# PCB_Cajero_10.net
KiCad netlist of a schematic drawn in EAGLE
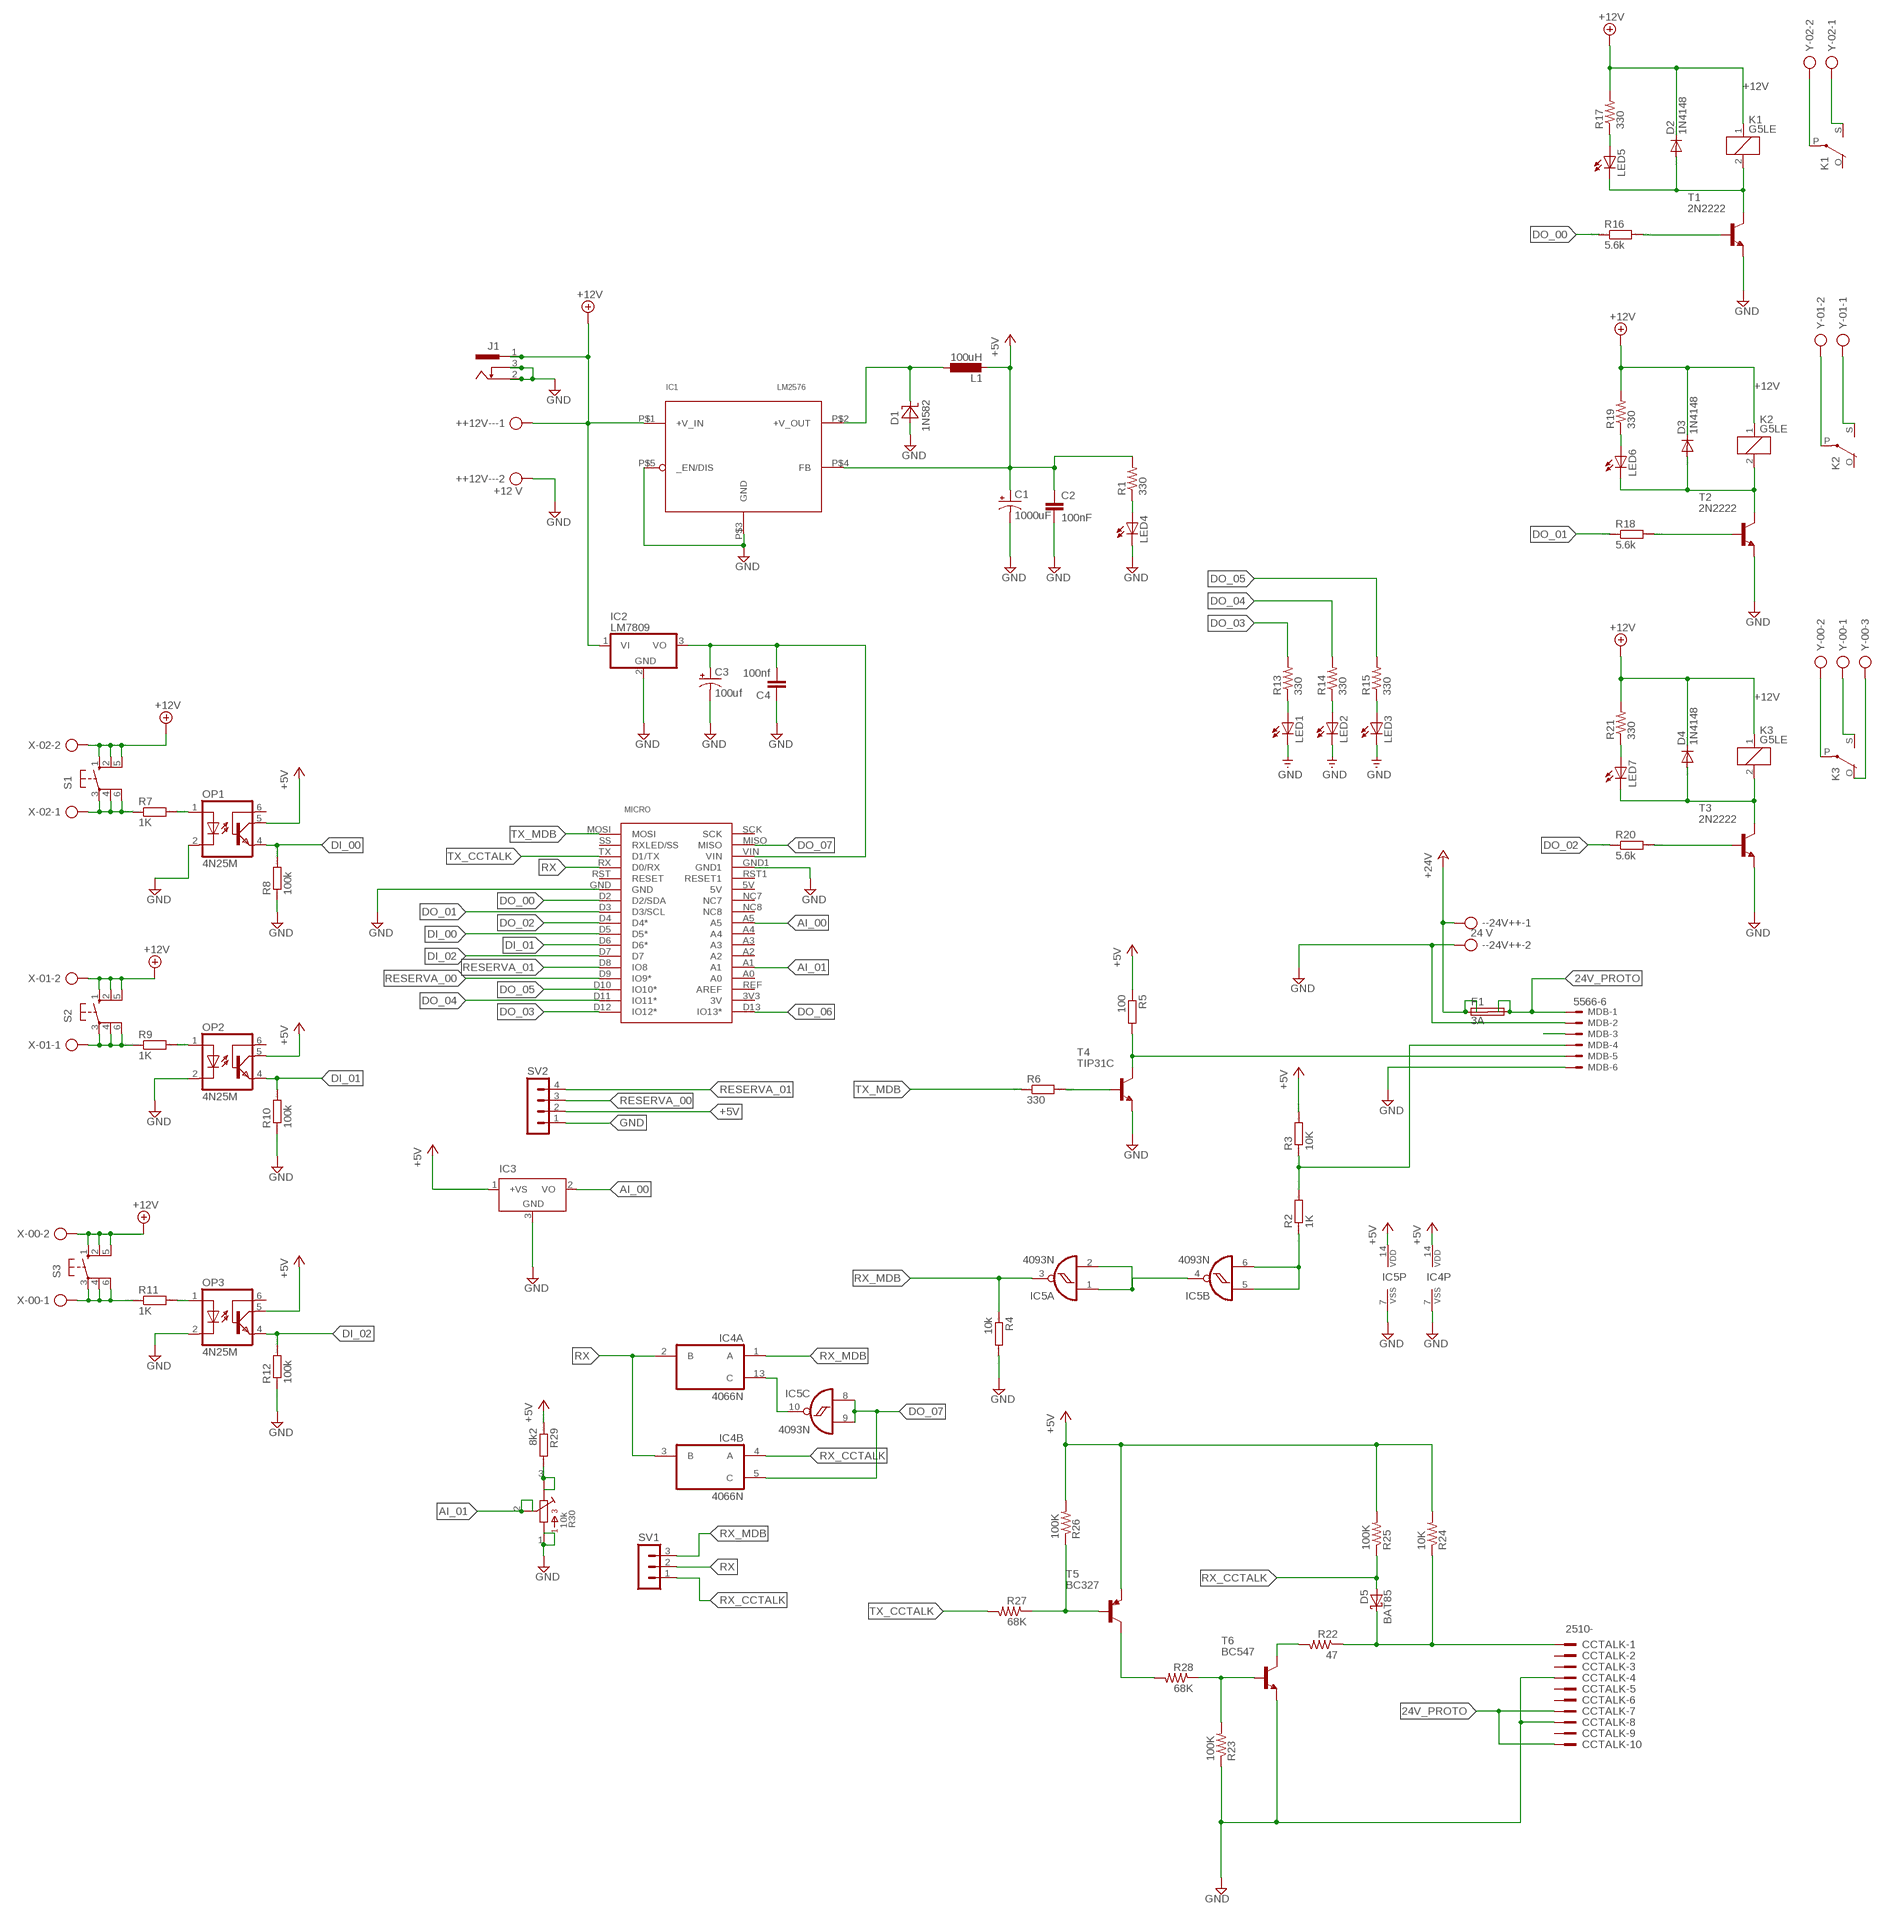
[diagram p0: schematic, sheet 1]

(export (version "E")
  (design (tool "Eeschema 10.0.6"))
  (components
    (comp (ref "++12V--")
      (value "+12 V")
      (footprint "eagle-import:AK500_2")
      (libsource (lib "eagle-import") (part "AK500/2"))
    )
    (comp (ref "--24V++")
      (value "24 V")
      (footprint "eagle-import:AK500_2")
      (libsource (lib "eagle-import") (part "AK500/2"))
    )
    (comp (ref "C1")
      (value "1000uF")
      (footprint "eagle-import:E5-5")
      (libsource (lib "eagle-import") (part "rcl_334_CPOL-USE5-5"))
    )
    (comp (ref "C2")
      (value "100nF")
      (footprint "eagle-import:C2.5-3")
      (libsource (lib "eagle-import") (part "C2,5-3"))
    )
    (comp (ref "C3")
      (value "100uf")
      (footprint "eagle-import:E2,5-6")
      (libsource (lib "eagle-import") (part "CPOL-USE2.5-6"))
    )
    (comp (ref "C4")
      (value "100nf")
      (footprint "eagle-import:C2.5-3")
      (libsource (lib "eagle-import") (part "C2,5-3"))
    )
    (comp (ref "CCTALK")
      (value "2510-")
      (footprint "eagle-import:PAK100_2500-10")
      (fields (field (name "MF") "3M") (field (name "MPN") "2510-6002UB"))
      (libsource (lib "eagle-import") (part "2510-"))
    )
    (comp (ref "D1")
      (value "1N582")
      (footprint "eagle-import:1N582_")
      (libsource (lib "eagle-import") (part "1N582"))
    )
    (comp (ref "D2")
      (value "1N4148")
      (footprint "eagle-import:DO35-7")
      (libsource (lib "eagle-import") (part "1N4148DO35-7"))
    )
    (comp (ref "D3")
      (value "1N4148")
      (footprint "eagle-import:DO35-7")
      (libsource (lib "eagle-import") (part "1N4148DO35-7"))
    )
    (comp (ref "D4")
      (value "1N4148")
      (footprint "eagle-import:DO35-7")
      (libsource (lib "eagle-import") (part "1N4148DO35-7"))
    )
    (comp (ref "D5")
      (value "BAT85")
      (footprint "eagle-import:SOD68")
      (libsource (lib "eagle-import") (part "BAT85"))
    )
    (comp (ref "F1")
      (value "3A")
      (footprint "eagle-import:SHK20L")
      (libsource (lib "eagle-import") (part "SHK20L"))
    )
    (comp (ref "IC1")
      (value "LM2576")
      (footprint "eagle-import:TO220_SEP")
      (libsource (lib "eagle-import") (part "LM2576-T05E"))
    )
    (comp (ref "IC2")
      (value "LM7809")
      (footprint "eagle-import:TO-220V")
      (libsource (lib "eagle-import") (part "LM7809"))
    )
    (comp (ref "IC3")
      (value "LM35CZ")
      (footprint "eagle-import:TO92")
      (libsource (lib "eagle-import") (part "LM35CZ"))
    )
    (comp (ref "IC4")
      (value "4066N")
      (footprint "eagle-import:DIL14")
      (libsource (lib "eagle-import") (part "4066N"))
    )
    (comp (ref "IC5")
      (value "4093N")
      (footprint "eagle-import:DIL14")
      (fields (field (name "SPICEPREFIX") "J"))
      (libsource (lib "eagle-import") (part "4093N"))
    )
    (comp (ref "J1")
      (value "KLDVX-0202-A")
      (footprint "eagle-import:KLDVX-0202-A")
      (libsource (lib "eagle-import") (part "KLDVX-0202-A"))
    )
    (comp (ref "K1")
      (value "G5LE")
      (footprint "eagle-import:G5LE")
      (libsource (lib "eagle-import") (part "G5LE"))
    )
    (comp (ref "K2")
      (value "G5LE")
      (footprint "eagle-import:G5LE")
      (libsource (lib "eagle-import") (part "G5LE"))
    )
    (comp (ref "K3")
      (value "G5LE")
      (footprint "eagle-import:G5LE")
      (libsource (lib "eagle-import") (part "G5LE"))
    )
    (comp (ref "L1")
      (value "100uH")
      (footprint "eagle-import:DO3316P")
      (libsource (lib "eagle-import") (part "DO3316P"))
    )
    (comp (ref "LED1")
      (value "LED5MM")
      (footprint "eagle-import:LED5MM")
      (libsource (lib "eagle-import") (part "LED5MM"))
    )
    (comp (ref "LED2")
      (value "LED5MM")
      (footprint "eagle-import:LED5MM")
      (libsource (lib "eagle-import") (part "LED5MM"))
    )
    (comp (ref "LED3")
      (value "LED5MM")
      (footprint "eagle-import:LED5MM")
      (libsource (lib "eagle-import") (part "LED5MM"))
    )
    (comp (ref "LED4")
      (value "LED5MM")
      (footprint "eagle-import:LED5MM")
      (libsource (lib "eagle-import") (part "LED5MM"))
    )
    (comp (ref "LED5")
      (value "LED5MM")
      (footprint "eagle-import:LED5MM")
      (libsource (lib "eagle-import") (part "LED5MM"))
    )
    (comp (ref "LED6")
      (value "LED5MM")
      (footprint "eagle-import:LED5MM")
      (libsource (lib "eagle-import") (part "LED5MM"))
    )
    (comp (ref "LED7")
      (value "LED5MM")
      (footprint "eagle-import:LED5MM")
      (libsource (lib "eagle-import") (part "LED5MM"))
    )
    (comp (ref "MDB")
      (value "5566-6")
      (footprint "eagle-import:5566-6")
      (fields (field (name "MF") "MOLEX") (field (name "MPN") "95566-61002"))
      (libsource (lib "eagle-import") (part "5566-6"))
    )
    (comp (ref "MICRO")
      (value "ARDUINO_MICROFOOTPRINT")
      (footprint "eagle-import:ARDUINO-MICRO")
      (libsource (lib "eagle-import") (part "ARDUINO_MICROFOOTPRINT"))
    )
    (comp (ref "OP1")
      (value "4N25M")
      (footprint "eagle-import:DIL06")
      (fields (field (name "MPN") "4N25-M"))
      (libsource (lib "eagle-import") (part "4N?M25"))
    )
    (comp (ref "OP2")
      (value "4N25M")
      (footprint "eagle-import:DIL06")
      (fields (field (name "MPN") "4N25-M"))
      (libsource (lib "eagle-import") (part "4N?M25"))
    )
    (comp (ref "OP3")
      (value "4N25M")
      (footprint "eagle-import:DIL06")
      (fields (field (name "MPN") "4N25-M"))
      (libsource (lib "eagle-import") (part "4N?M25"))
    )
    (comp (ref "R1")
      (value "330")
      (footprint "eagle-import:0207_7")
      (libsource (lib "eagle-import") (part "R-US_0207/7"))
    )
    (comp (ref "R2")
      (value "1K")
      (footprint "eagle-import:0204_7")
      (libsource (lib "eagle-import") (part "R0204/7"))
    )
    (comp (ref "R3")
      (value "10K")
      (footprint "eagle-import:0204_7")
      (libsource (lib "eagle-import") (part "R0204/7"))
    )
    (comp (ref "R4")
      (value "10k")
      (footprint "eagle-import:0204_7")
      (libsource (lib "eagle-import") (part "R0204/7"))
    )
    (comp (ref "R5")
      (value "100")
      (footprint "eagle-import:0309_10")
      (libsource (lib "eagle-import") (part "R-EU_0309/10"))
    )
    (comp (ref "R6")
      (value "330")
      (footprint "eagle-import:0204_7")
      (libsource (lib "eagle-import") (part "R0204/7"))
    )
    (comp (ref "R7")
      (value "1K")
      (footprint "eagle-import:0204_7")
      (libsource (lib "eagle-import") (part "R0204/7"))
    )
    (comp (ref "R8")
      (value "100k")
      (footprint "eagle-import:0204_7")
      (libsource (lib "eagle-import") (part "R0204/7"))
    )
    (comp (ref "R9")
      (value "1K")
      (footprint "eagle-import:0204_7")
      (libsource (lib "eagle-import") (part "R0204/7"))
    )
    (comp (ref "R10")
      (value "100k")
      (footprint "eagle-import:0204_7")
      (libsource (lib "eagle-import") (part "R0204/7"))
    )
    (comp (ref "R11")
      (value "1K")
      (footprint "eagle-import:0204_7")
      (libsource (lib "eagle-import") (part "R0204/7"))
    )
    (comp (ref "R12")
      (value "100k")
      (footprint "eagle-import:0204_7")
      (libsource (lib "eagle-import") (part "R0204/7"))
    )
    (comp (ref "R13")
      (value "330")
      (footprint "eagle-import:0207_7")
      (libsource (lib "eagle-import") (part "R-US_0207/7"))
    )
    (comp (ref "R14")
      (value "330")
      (footprint "eagle-import:0207_7")
      (libsource (lib "eagle-import") (part "R-US_0207/7"))
    )
    (comp (ref "R15")
      (value "330")
      (footprint "eagle-import:0207_7")
      (libsource (lib "eagle-import") (part "R-US_0207/7"))
    )
    (comp (ref "R16")
      (value "5.6k")
      (footprint "eagle-import:0204_7")
      (libsource (lib "eagle-import") (part "R0204/7"))
    )
    (comp (ref "R17")
      (value "330")
      (footprint "eagle-import:0207_7")
      (libsource (lib "eagle-import") (part "R-US_0207/7"))
    )
    (comp (ref "R18")
      (value "5.6k")
      (footprint "eagle-import:0204_7")
      (libsource (lib "eagle-import") (part "R0204/7"))
    )
    (comp (ref "R19")
      (value "330")
      (footprint "eagle-import:0207_7")
      (libsource (lib "eagle-import") (part "R-US_0207/7"))
    )
    (comp (ref "R20")
      (value "5.6k")
      (footprint "eagle-import:0204_7")
      (libsource (lib "eagle-import") (part "R0204/7"))
    )
    (comp (ref "R21")
      (value "330")
      (footprint "eagle-import:0207_7")
      (libsource (lib "eagle-import") (part "R-US_0207/7"))
    )
    (comp (ref "R22")
      (value "47")
      (footprint "eagle-import:0204_7")
      (libsource (lib "eagle-import") (part "R-US_0204/7"))
    )
    (comp (ref "R23")
      (value "100K")
      (footprint "eagle-import:0204_7")
      (libsource (lib "eagle-import") (part "R-US_0204/7"))
    )
    (comp (ref "R24")
      (value "10K")
      (footprint "eagle-import:0204_7")
      (libsource (lib "eagle-import") (part "R-US_0204/7"))
    )
    (comp (ref "R25")
      (value "100K")
      (footprint "eagle-import:0204_7")
      (libsource (lib "eagle-import") (part "R-US_0204/7"))
    )
    (comp (ref "R26")
      (value "100K")
      (footprint "eagle-import:0204_7")
      (libsource (lib "eagle-import") (part "R-US_0204/7"))
    )
    (comp (ref "R27")
      (value "68K")
      (footprint "eagle-import:0204_7")
      (libsource (lib "eagle-import") (part "R-US_0204/7"))
    )
    (comp (ref "R28")
      (value "68K")
      (footprint "eagle-import:0204_7")
      (libsource (lib "eagle-import") (part "R-US_0204/7"))
    )
    (comp (ref "R29")
      (value "8k2")
      (footprint "eagle-import:0204_7")
      (libsource (lib "eagle-import") (part "R0204/7"))
    )
    (comp (ref "R30")
      (value "10k")
      (footprint "eagle-import:3386-MULTI")
      (libsource (lib "eagle-import") (part "3386"))
    )
    (comp (ref "S1")
      (value "10-XX")
      (footprint "eagle-import:B3F-10XX")
      (fields (field (name "MPN") "B3F-1000"))
      (libsource (lib "eagle-import") (part "10-XX"))
    )
    (comp (ref "S2")
      (value "10-XX")
      (footprint "eagle-import:B3F-10XX")
      (fields (field (name "MPN") "B3F-1000"))
      (libsource (lib "eagle-import") (part "10-XX"))
    )
    (comp (ref "S3")
      (value "10-XX")
      (footprint "eagle-import:B3F-10XX")
      (fields (field (name "MPN") "B3F-1000"))
      (libsource (lib "eagle-import") (part "10-XX"))
    )
    (comp (ref "SV1")
      (value "MA03-1")
      (footprint "eagle-import:MA03-1")
      (libsource (lib "eagle-import") (part "MA03-1"))
    )
    (comp (ref "SV2")
      (value "MA04-1")
      (footprint "eagle-import:MA04-1")
      (libsource (lib "eagle-import") (part "MA04-1"))
    )
    (comp (ref "T1")
      (value "2N2222")
      (footprint "eagle-import:TO18")
      (libsource (lib "eagle-import") (part "2N2222"))
    )
    (comp (ref "T2")
      (value "2N2222")
      (footprint "eagle-import:TO18")
      (libsource (lib "eagle-import") (part "2N2222"))
    )
    (comp (ref "T3")
      (value "2N2222")
      (footprint "eagle-import:TO18")
      (libsource (lib "eagle-import") (part "2N2222"))
    )
    (comp (ref "T4")
      (value "TIP31C")
      (footprint "eagle-import:TO-220V")
      (libsource (lib "eagle-import") (part "TIP31C"))
    )
    (comp (ref "T5")
      (value "BC327")
      (footprint "eagle-import:TO92")
      (libsource (lib "eagle-import") (part "BC327"))
    )
    (comp (ref "T6")
      (value "BC547")
      (footprint "eagle-import:TO92")
      (libsource (lib "eagle-import") (part "BC547"))
    )
    (comp (ref "X-00")
      (value "AK500/2")
      (footprint "eagle-import:AK500_2")
      (libsource (lib "eagle-import") (part "AK500/2"))
    )
    (comp (ref "X-01")
      (value "AK500/2")
      (footprint "eagle-import:AK500_2")
      (libsource (lib "eagle-import") (part "AK500/2"))
    )
    (comp (ref "X-02")
      (value "AK500/2")
      (footprint "eagle-import:AK500_2")
      (libsource (lib "eagle-import") (part "AK500/2"))
    )
    (comp (ref "Y-00")
      (value "AK500/3")
      (footprint "eagle-import:AK500_3")
      (libsource (lib "eagle-import") (part "AK500/3"))
    )
    (comp (ref "Y-01")
      (value "AK500/2")
      (footprint "eagle-import:AK500_2")
      (libsource (lib "eagle-import") (part "AK500/2"))
    )
    (comp (ref "Y-02")
      (value "AK500/2")
      (footprint "eagle-import:AK500_2")
      (libsource (lib "eagle-import") (part "AK500/2"))
    )
  )
  (nets
    (net (code "1") (name "+5V") (class "Default")
      (node (ref "C1") (pin "+") (pinfunction "+_+") (pintype "passive"))
      (node (ref "C2") (pin "1") (pinfunction "1_1") (pintype "passive"))
      (node (ref "IC1") (pin "P$4") (pinfunction "FB_P$4") (pintype "input"))
      (node (ref "IC3") (pin "1") (pinfunction "+VS_1") (pintype "input"))
      (node (ref "IC4") (pin "14") (pinfunction "VDD_14") (pintype "power_in"))
      (node (ref "IC5") (pin "14") (pinfunction "VDD_14") (pintype "power_in"))
      (node (ref "L1") (pin "1") (pinfunction "1_1") (pintype "passive"))
      (node (ref "OP1") (pin "5") (pinfunction "COL_5") (pintype "passive"))
      (node (ref "OP2") (pin "5") (pinfunction "COL_5") (pintype "passive"))
      (node (ref "OP3") (pin "5") (pinfunction "COL_5") (pintype "passive"))
      (node (ref "R1") (pin "2") (pinfunction "2_2") (pintype "passive"))
      (node (ref "R24") (pin "2") (pinfunction "2_2") (pintype "passive"))
      (node (ref "R25") (pin "2") (pinfunction "2_2") (pintype "passive"))
      (node (ref "R26") (pin "2") (pinfunction "2_2") (pintype "passive"))
      (node (ref "R29") (pin "1") (pinfunction "1_1") (pintype "passive"))
      (node (ref "R3") (pin "2") (pinfunction "2_2") (pintype "passive"))
      (node (ref "R5") (pin "1") (pinfunction "1_1") (pintype "passive"))
      (node (ref "SV2") (pin "2") (pinfunction "2_2") (pintype "passive"))
      (node (ref "T5") (pin "1") (pinfunction "E_1") (pintype "passive"))
    )
    (net (code "2") (name "+12V") (class "Default")
      (node (ref "++12V--") (pin "1") (pinfunction "KL_1") (pintype "passive"))
      (node (ref "D2") (pin "C") (pinfunction "C_C") (pintype "passive"))
      (node (ref "D3") (pin "C") (pinfunction "C_C") (pintype "passive"))
      (node (ref "D4") (pin "C") (pinfunction "C_C") (pintype "passive"))
      (node (ref "IC1") (pin "P$1") (pinfunction "+V_IN_P$1") (pintype "input"))
      (node (ref "IC2") (pin "1") (pinfunction "VI_1") (pintype "input"))
      (node (ref "J1") (pin "1") (pinfunction "1_1") (pintype "passive"))
      (node (ref "J1") (pin "1@1") (pinfunction "1_1@1") (pintype "passive"))
      (node (ref "K1") (pin "1") (pinfunction "1_1") (pintype "passive"))
      (node (ref "K2") (pin "1") (pinfunction "1_1") (pintype "passive"))
      (node (ref "K3") (pin "1") (pinfunction "1_1") (pintype "passive"))
      (node (ref "R17") (pin "2") (pinfunction "2_2") (pintype "passive"))
      (node (ref "R19") (pin "2") (pinfunction "2_2") (pintype "passive"))
      (node (ref "R21") (pin "2") (pinfunction "2_2") (pintype "passive"))
      (node (ref "S1") (pin "1") (pinfunction "S_1") (pintype "passive"))
      (node (ref "S1") (pin "2") (pinfunction "S1_2") (pintype "passive"))
      (node (ref "S1") (pin "5") (pinfunction "S2_5") (pintype "passive"))
      (node (ref "S2") (pin "1") (pinfunction "S_1") (pintype "passive"))
      (node (ref "S2") (pin "2") (pinfunction "S1_2") (pintype "passive"))
      (node (ref "S2") (pin "5") (pinfunction "S2_5") (pintype "passive"))
      (node (ref "S3") (pin "1") (pinfunction "S_1") (pintype "passive"))
      (node (ref "S3") (pin "2") (pinfunction "S1_2") (pintype "passive"))
      (node (ref "S3") (pin "5") (pinfunction "S2_5") (pintype "passive"))
      (node (ref "X-00") (pin "2") (pinfunction "KL_2") (pintype "passive"))
      (node (ref "X-01") (pin "2") (pinfunction "KL_2") (pintype "passive"))
      (node (ref "X-02") (pin "2") (pinfunction "KL_2") (pintype "passive"))
    )
    (net (code "3") (name "+24V") (class "Default")
      (node (ref "--24V++") (pin "1") (pinfunction "KL_1") (pintype "passive"))
      (node (ref "F1") (pin "1A") (pinfunction "1A_1A") (pintype "passive"))
      (node (ref "F1") (pin "1B") (pinfunction "1B_1B") (pintype "passive"))
    )
    (net (code "4") (name "24V_PROTO") (class "Default")
      (node (ref "CCTALK") (pin "10") (pinfunction "KL_10") (pintype "passive"))
      (node (ref "CCTALK") (pin "7") (pinfunction "KL_7") (pintype "passive"))
      (node (ref "F1") (pin "2A") (pinfunction "2A_2A") (pintype "passive"))
      (node (ref "F1") (pin "2B") (pinfunction "2B_2B") (pintype "passive"))
      (node (ref "MDB") (pin "1") (pinfunction "S_1") (pintype "passive"))
    )
    (net (code "5") (name "AI_00") (class "Default")
      (node (ref "IC3") (pin "2") (pinfunction "VO_2") (pintype "input"))
      (node (ref "MICRO") (pin "A5") (pinfunction "A5_A5") (pintype "bidirectional"))
    )
    (net (code "6") (name "AI_01") (class "Default")
      (node (ref "MICRO") (pin "A1") (pinfunction "A1_A1") (pintype "bidirectional"))
      (node (ref "R30") (pin "2") (pinfunction "2_2") (pintype "passive"))
      (node (ref "R30") (pin "5") (pinfunction "5_5") (pintype "passive"))
    )
    (net (code "7") (name "DI_00") (class "Default")
      (node (ref "MICRO") (pin "D5") (pinfunction "D5*_D5") (pintype "bidirectional"))
      (node (ref "OP1") (pin "4") (pinfunction "EMI_4") (pintype "passive"))
      (node (ref "R8") (pin "2") (pinfunction "2_2") (pintype "passive"))
    )
    (net (code "8") (name "DI_01") (class "Default")
      (node (ref "MICRO") (pin "D6") (pinfunction "D6*_D6") (pintype "bidirectional"))
      (node (ref "OP2") (pin "4") (pinfunction "EMI_4") (pintype "passive"))
      (node (ref "R10") (pin "2") (pinfunction "2_2") (pintype "passive"))
    )
    (net (code "9") (name "DI_02") (class "Default")
      (node (ref "MICRO") (pin "D7") (pinfunction "D7_D7") (pintype "bidirectional"))
      (node (ref "OP3") (pin "4") (pinfunction "EMI_4") (pintype "passive"))
      (node (ref "R12") (pin "2") (pinfunction "2_2") (pintype "passive"))
    )
    (net (code "10") (name "DO_00") (class "Default")
      (node (ref "MICRO") (pin "D2") (pinfunction "D2/SDA_D2") (pintype "bidirectional"))
      (node (ref "R16") (pin "1") (pinfunction "1_1") (pintype "passive"))
    )
    (net (code "11") (name "DO_01") (class "Default")
      (node (ref "MICRO") (pin "D3") (pinfunction "D3/SCL_D3") (pintype "bidirectional"))
      (node (ref "R18") (pin "1") (pinfunction "1_1") (pintype "passive"))
    )
    (net (code "12") (name "DO_02") (class "Default")
      (node (ref "MICRO") (pin "D4") (pinfunction "D4*_D4") (pintype "bidirectional"))
      (node (ref "R20") (pin "1") (pinfunction "1_1") (pintype "passive"))
    )
    (net (code "13") (name "DO_03") (class "Default")
      (node (ref "MICRO") (pin "D12") (pinfunction "IO12*_D12") (pintype "bidirectional"))
      (node (ref "R13") (pin "2") (pinfunction "2_2") (pintype "passive"))
    )
    (net (code "14") (name "DO_04") (class "Default")
      (node (ref "MICRO") (pin "D11") (pinfunction "IO11*_D11") (pintype "bidirectional"))
      (node (ref "R14") (pin "2") (pinfunction "2_2") (pintype "passive"))
    )
    (net (code "15") (name "DO_05") (class "Default")
      (node (ref "MICRO") (pin "D10") (pinfunction "IO10*_D10") (pintype "bidirectional"))
      (node (ref "R15") (pin "2") (pinfunction "2_2") (pintype "passive"))
    )
    (net (code "16") (name "DO_06") (class "Default")
      (node (ref "MICRO") (pin "D13") (pinfunction "IO13*_D13") (pintype "bidirectional"))
    )
    (net (code "17") (name "DO_07") (class "Default")
      (node (ref "IC4") (pin "5") (pinfunction "C_5") (pintype "input"))
      (node (ref "IC5") (pin "8") (pinfunction "I0_8") (pintype "input"))
      (node (ref "IC5") (pin "9") (pinfunction "I1_9") (pintype "input"))
      (node (ref "MICRO") (pin "MISO") (pinfunction "MISO_MISO") (pintype "bidirectional"))
    )
    (net (code "18") (name "GND") (class "Default")
      (node (ref "++12V--") (pin "2") (pinfunction "KL_2") (pintype "passive"))
      (node (ref "--24V++") (pin "2") (pinfunction "KL_2") (pintype "passive"))
      (node (ref "C1") (pin "-") (pinfunction "-_-") (pintype "passive"))
      (node (ref "C2") (pin "2") (pinfunction "2_2") (pintype "passive"))
      (node (ref "C3") (pin "-") (pinfunction "-_-") (pintype "passive"))
      (node (ref "C4") (pin "1") (pinfunction "1_1") (pintype "passive"))
      (node (ref "CCTALK") (pin "4") (pinfunction "KL_4") (pintype "passive"))
      (node (ref "CCTALK") (pin "8") (pinfunction "KL_8") (pintype "passive"))
      (node (ref "D1") (pin "A") (pinfunction "A_A") (pintype "passive"))
      (node (ref "IC1") (pin "P$3") (pinfunction "GND_P$3") (pintype "power_in"))
      (node (ref "IC1") (pin "P$5") (pinfunction "_EN/DIS_P$5") (pintype "input"))
      (node (ref "IC2") (pin "2") (pinfunction "GND_2") (pintype "passive"))
      (node (ref "IC3") (pin "3") (pinfunction "GND_3") (pintype "power_in"))
      (node (ref "IC4") (pin "7") (pinfunction "VSS_7") (pintype "power_in"))
      (node (ref "IC5") (pin "7") (pinfunction "VSS_7") (pintype "power_in"))
      (node (ref "J1") (pin "2") (pinfunction "2_2") (pintype "passive"))
      (node (ref "J1") (pin "2@1") (pinfunction "2_2@1") (pintype "passive"))
      (node (ref "J1") (pin "3") (pinfunction "3_3") (pintype "passive"))
      (node (ref "J1") (pin "3@1") (pinfunction "3_3@1") (pintype "passive"))
      (node (ref "LED1") (pin "K") (pinfunction "C_K") (pintype "passive"))
      (node (ref "LED2") (pin "K") (pinfunction "C_K") (pintype "passive"))
      (node (ref "LED3") (pin "K") (pinfunction "C_K") (pintype "passive"))
      (node (ref "LED4") (pin "K") (pinfunction "C_K") (pintype "passive"))
      (node (ref "MDB") (pin "2") (pinfunction "S_2") (pintype "passive"))
      (node (ref "MDB") (pin "6") (pinfunction "S_6") (pintype "passive"))
      (node (ref "MICRO") (pin "GND") (pinfunction "GND_GND") (pintype "bidirectional"))
      (node (ref "MICRO") (pin "GND1") (pinfunction "GND1_GND1") (pintype "bidirectional"))
      (node (ref "OP1") (pin "2") (pinfunction "C_2") (pintype "passive"))
      (node (ref "OP2") (pin "2") (pinfunction "C_2") (pintype "passive"))
      (node (ref "OP3") (pin "2") (pinfunction "C_2") (pintype "passive"))
      (node (ref "R10") (pin "1") (pinfunction "1_1") (pintype "passive"))
      (node (ref "R12") (pin "1") (pinfunction "1_1") (pintype "passive"))
      (node (ref "R23") (pin "1") (pinfunction "1_1") (pintype "passive"))
      (node (ref "R30") (pin "1") (pinfunction "1_1") (pintype "passive"))
      (node (ref "R30") (pin "4") (pinfunction "4_4") (pintype "passive"))
      (node (ref "R4") (pin "2") (pinfunction "2_2") (pintype "passive"))
      (node (ref "R8") (pin "1") (pinfunction "1_1") (pintype "passive"))
      (node (ref "SV2") (pin "1") (pinfunction "1_1") (pintype "passive"))
      (node (ref "T1") (pin "1") (pinfunction "E_1") (pintype "passive"))
      (node (ref "T2") (pin "1") (pinfunction "E_1") (pintype "passive"))
      (node (ref "T3") (pin "1") (pinfunction "E_1") (pintype "passive"))
      (node (ref "T4") (pin "3") (pinfunction "E_3") (pintype "passive"))
      (node (ref "T6") (pin "1") (pinfunction "E_1") (pintype "passive"))
    )
    (net (code "19") (name "Net-(CCTALKA-KL)") (class "Default")
      (node (ref "CCTALK") (pin "1") (pinfunction "KL_1") (pintype "passive"))
      (node (ref "D5") (pin "C") (pinfunction "K_C") (pintype "passive"))
      (node (ref "R22") (pin "1") (pinfunction "1_1") (pintype "passive"))
      (node (ref "R24") (pin "1") (pinfunction "1_1") (pintype "passive"))
    )
    (net (code "20") (name "Net-(IC1-+V_OUT)") (class "Default")
      (node (ref "D1") (pin "C") (pinfunction "C_C") (pintype "passive"))
      (node (ref "IC1") (pin "P$2") (pinfunction "+V_OUT_P$2") (pintype "output"))
      (node (ref "L1") (pin "2") (pinfunction "2_2") (pintype "passive"))
    )
    (net (code "21") (name "Net-(IC2-VO)") (class "Default")
      (node (ref "C3") (pin "+") (pinfunction "+_+") (pintype "passive"))
      (node (ref "C4") (pin "2") (pinfunction "2_2") (pintype "passive"))
      (node (ref "IC2") (pin "3") (pinfunction "VO_3") (pintype "passive"))
      (node (ref "MICRO") (pin "VIN") (pinfunction "VIN_VIN") (pintype "bidirectional"))
    )
    (net (code "22") (name "Net-(IC4A-C)") (class "Default")
      (node (ref "IC4") (pin "13") (pinfunction "C_13") (pintype "input"))
      (node (ref "IC5") (pin "10") (pinfunction "O_10") (pintype "output"))
    )
    (net (code "23") (name "Net-(IC5A-I0)") (class "Default")
      (node (ref "IC5") (pin "1") (pinfunction "I0_1") (pintype "input"))
      (node (ref "IC5") (pin "2") (pinfunction "I1_2") (pintype "input"))
      (node (ref "IC5") (pin "4") (pinfunction "O_4") (pintype "output"))
    )
    (net (code "24") (name "Net-(IC5B-I0)") (class "Default")
      (node (ref "IC5") (pin "5") (pinfunction "I0_5") (pintype "input"))
      (node (ref "IC5") (pin "6") (pinfunction "I1_6") (pintype "input"))
      (node (ref "R2") (pin "1") (pinfunction "1_1") (pintype "passive"))
    )
    (net (code "25") (name "Net-(LED1-PadA)") (class "Default")
      (node (ref "LED1") (pin "A") (pinfunction "A_A") (pintype "passive"))
      (node (ref "R13") (pin "1") (pinfunction "1_1") (pintype "passive"))
    )
    (net (code "26") (name "Net-(LED2-PadA)") (class "Default")
      (node (ref "LED2") (pin "A") (pinfunction "A_A") (pintype "passive"))
      (node (ref "R14") (pin "1") (pinfunction "1_1") (pintype "passive"))
    )
    (net (code "27") (name "Net-(LED3-PadA)") (class "Default")
      (node (ref "LED3") (pin "A") (pinfunction "A_A") (pintype "passive"))
      (node (ref "R15") (pin "1") (pinfunction "1_1") (pintype "passive"))
    )
    (net (code "28") (name "Net-(LED4-PadA)") (class "Default")
      (node (ref "LED4") (pin "A") (pinfunction "A_A") (pintype "passive"))
      (node (ref "R1") (pin "1") (pinfunction "1_1") (pintype "passive"))
    )
    (net (code "29") (name "Net-(LED5-C)") (class "Default")
      (node (ref "D2") (pin "A") (pinfunction "A_A") (pintype "passive"))
      (node (ref "K1") (pin "2") (pinfunction "2_2") (pintype "passive"))
      (node (ref "LED5") (pin "K") (pinfunction "C_K") (pintype "passive"))
      (node (ref "T1") (pin "3") (pinfunction "C_3") (pintype "passive"))
    )
    (net (code "30") (name "Net-(LED5-PadA)") (class "Default")
      (node (ref "LED5") (pin "A") (pinfunction "A_A") (pintype "passive"))
      (node (ref "R17") (pin "1") (pinfunction "1_1") (pintype "passive"))
    )
    (net (code "31") (name "Net-(LED6-C)") (class "Default")
      (node (ref "D3") (pin "A") (pinfunction "A_A") (pintype "passive"))
      (node (ref "K2") (pin "2") (pinfunction "2_2") (pintype "passive"))
      (node (ref "LED6") (pin "K") (pinfunction "C_K") (pintype "passive"))
      (node (ref "T2") (pin "3") (pinfunction "C_3") (pintype "passive"))
    )
    (net (code "32") (name "Net-(LED6-PadA)") (class "Default")
      (node (ref "LED6") (pin "A") (pinfunction "A_A") (pintype "passive"))
      (node (ref "R19") (pin "1") (pinfunction "1_1") (pintype "passive"))
    )
    (net (code "33") (name "Net-(LED7-C)") (class "Default")
      (node (ref "D4") (pin "A") (pinfunction "A_A") (pintype "passive"))
      (node (ref "K3") (pin "2") (pinfunction "2_2") (pintype "passive"))
      (node (ref "LED7") (pin "K") (pinfunction "C_K") (pintype "passive"))
      (node (ref "T3") (pin "3") (pinfunction "C_3") (pintype "passive"))
    )
    (net (code "34") (name "Net-(LED7-PadA)") (class "Default")
      (node (ref "LED7") (pin "A") (pinfunction "A_A") (pintype "passive"))
      (node (ref "R21") (pin "1") (pinfunction "1_1") (pintype "passive"))
    )
    (net (code "35") (name "Net-(MDBD-S)") (class "Default")
      (node (ref "MDB") (pin "4") (pinfunction "S_4") (pintype "passive"))
      (node (ref "R2") (pin "2") (pinfunction "2_2") (pintype "passive"))
      (node (ref "R3") (pin "1") (pinfunction "1_1") (pintype "passive"))
    )
    (net (code "36") (name "Net-(MDBE-S)") (class "Default")
      (node (ref "MDB") (pin "5") (pinfunction "S_5") (pintype "passive"))
      (node (ref "R5") (pin "2") (pinfunction "2_2") (pintype "passive"))
      (node (ref "T4") (pin "2") (pinfunction "C_2") (pintype "passive"))
    )
    (net (code "37") (name "Net-(OP1-A)") (class "Default")
      (node (ref "OP1") (pin "1") (pinfunction "A_1") (pintype "passive"))
      (node (ref "R7") (pin "2") (pinfunction "2_2") (pintype "passive"))
    )
    (net (code "38") (name "Net-(OP2-A)") (class "Default")
      (node (ref "OP2") (pin "1") (pinfunction "A_1") (pintype "passive"))
      (node (ref "R9") (pin "2") (pinfunction "2_2") (pintype "passive"))
    )
    (net (code "39") (name "Net-(OP3-A)") (class "Default")
      (node (ref "OP3") (pin "1") (pinfunction "A_1") (pintype "passive"))
      (node (ref "R11") (pin "2") (pinfunction "2_2") (pintype "passive"))
    )
    (net (code "40") (name "Net-(R29-Pad2)") (class "Default")
      (node (ref "R29") (pin "2") (pinfunction "2_2") (pintype "passive"))
      (node (ref "R30") (pin "3") (pinfunction "3_3") (pintype "passive"))
      (node (ref "R30") (pin "6") (pinfunction "6_6") (pintype "passive"))
    )
    (net (code "41") (name "Net-(S1-P)") (class "Default")
      (node (ref "R7") (pin "1") (pinfunction "1_1") (pintype "passive"))
      (node (ref "S1") (pin "3") (pinfunction "P_3") (pintype "passive"))
      (node (ref "S1") (pin "4") (pinfunction "P1_4") (pintype "passive"))
      (node (ref "S1") (pin "6") (pinfunction "P2_6") (pintype "passive"))
      (node (ref "X-02") (pin "1") (pinfunction "KL_1") (pintype "passive"))
    )
    (net (code "42") (name "Net-(S2-P)") (class "Default")
      (node (ref "R9") (pin "1") (pinfunction "1_1") (pintype "passive"))
      (node (ref "S2") (pin "3") (pinfunction "P_3") (pintype "passive"))
      (node (ref "S2") (pin "4") (pinfunction "P1_4") (pintype "passive"))
      (node (ref "S2") (pin "6") (pinfunction "P2_6") (pintype "passive"))
      (node (ref "X-01") (pin "1") (pinfunction "KL_1") (pintype "passive"))
    )
    (net (code "43") (name "Net-(S3-P)") (class "Default")
      (node (ref "R11") (pin "1") (pinfunction "1_1") (pintype "passive"))
      (node (ref "S3") (pin "3") (pinfunction "P_3") (pintype "passive"))
      (node (ref "S3") (pin "4") (pinfunction "P1_4") (pintype "passive"))
      (node (ref "S3") (pin "6") (pinfunction "P2_6") (pintype "passive"))
      (node (ref "X-00") (pin "1") (pinfunction "KL_1") (pintype "passive"))
    )
    (net (code "44") (name "Net-(T1-B)") (class "Default")
      (node (ref "R16") (pin "2") (pinfunction "2_2") (pintype "passive"))
      (node (ref "T1") (pin "2") (pinfunction "B_2") (pintype "passive"))
    )
    (net (code "45") (name "Net-(T2-B)") (class "Default")
      (node (ref "R18") (pin "2") (pinfunction "2_2") (pintype "passive"))
      (node (ref "T2") (pin "2") (pinfunction "B_2") (pintype "passive"))
    )
    (net (code "46") (name "Net-(T3-B)") (class "Default")
      (node (ref "R20") (pin "2") (pinfunction "2_2") (pintype "passive"))
      (node (ref "T3") (pin "2") (pinfunction "B_2") (pintype "passive"))
    )
    (net (code "47") (name "Net-(T4-B)") (class "Default")
      (node (ref "R6") (pin "2") (pinfunction "2_2") (pintype "passive"))
      (node (ref "T4") (pin "1") (pinfunction "B_1") (pintype "passive"))
    )
    (net (code "48") (name "Net-(T5-B)") (class "Default")
      (node (ref "R26") (pin "1") (pinfunction "1_1") (pintype "passive"))
      (node (ref "R27") (pin "1") (pinfunction "1_1") (pintype "passive"))
      (node (ref "T5") (pin "2") (pinfunction "B_2") (pintype "passive"))
    )
    (net (code "49") (name "Net-(T5-C)") (class "Default")
      (node (ref "R28") (pin "2") (pinfunction "2_2") (pintype "passive"))
      (node (ref "T5") (pin "3") (pinfunction "C_3") (pintype "passive"))
    )
    (net (code "50") (name "Net-(T6-B)") (class "Default")
      (node (ref "R23") (pin "2") (pinfunction "2_2") (pintype "passive"))
      (node (ref "R28") (pin "1") (pinfunction "1_1") (pintype "passive"))
      (node (ref "T6") (pin "2") (pinfunction "B_2") (pintype "passive"))
    )
    (net (code "51") (name "Net-(T6-C)") (class "Default")
      (node (ref "R22") (pin "2") (pinfunction "2_2") (pintype "passive"))
      (node (ref "T6") (pin "3") (pinfunction "C_3") (pintype "passive"))
    )
    (net (code "52") (name "Net-(Y-00A-KL)") (class "Default")
      (node (ref "K3") (pin "S") (pinfunction "S_S") (pintype "passive"))
      (node (ref "Y-00") (pin "1") (pinfunction "KL_1") (pintype "passive"))
    )
    (net (code "53") (name "Net-(Y-00B-KL)") (class "Default")
      (node (ref "K3") (pin "P") (pinfunction "P_P") (pintype "passive"))
      (node (ref "Y-00") (pin "2") (pinfunction "KL_2") (pintype "passive"))
    )
    (net (code "54") (name "Net-(Y-00C-KL)") (class "Default")
      (node (ref "K3") (pin "O") (pinfunction "O_O") (pintype "passive"))
      (node (ref "Y-00") (pin "3") (pinfunction "KL_3") (pintype "passive"))
    )
    (net (code "55") (name "Net-(Y-01A-KL)") (class "Default")
      (node (ref "K2") (pin "S") (pinfunction "S_S") (pintype "passive"))
      (node (ref "Y-01") (pin "1") (pinfunction "KL_1") (pintype "passive"))
    )
    (net (code "56") (name "Net-(Y-01B-KL)") (class "Default")
      (node (ref "K2") (pin "P") (pinfunction "P_P") (pintype "passive"))
      (node (ref "Y-01") (pin "2") (pinfunction "KL_2") (pintype "passive"))
    )
    (net (code "57") (name "Net-(Y-02A-KL)") (class "Default")
      (node (ref "K1") (pin "S") (pinfunction "S_S") (pintype "passive"))
      (node (ref "Y-02") (pin "1") (pinfunction "KL_1") (pintype "passive"))
    )
    (net (code "58") (name "Net-(Y-02B-KL)") (class "Default")
      (node (ref "K1") (pin "P") (pinfunction "P_P") (pintype "passive"))
      (node (ref "Y-02") (pin "2") (pinfunction "KL_2") (pintype "passive"))
    )
    (net (code "59") (name "RESERVA_00") (class "Default")
      (node (ref "MICRO") (pin "D9") (pinfunction "IO9*_D9") (pintype "bidirectional"))
      (node (ref "SV2") (pin "3") (pinfunction "3_3") (pintype "passive"))
    )
    (net (code "60") (name "RESERVA_01") (class "Default")
      (node (ref "MICRO") (pin "D8") (pinfunction "IO8_D8") (pintype "bidirectional"))
      (node (ref "SV2") (pin "4") (pinfunction "4_4") (pintype "passive"))
    )
    (net (code "61") (name "RX") (class "Default")
      (node (ref "IC4") (pin "2") (pinfunction "B_2") (pintype "tri_state"))
      (node (ref "IC4") (pin "3") (pinfunction "B_3") (pintype "tri_state"))
      (node (ref "MICRO") (pin "RX") (pinfunction "D0/RX_RX") (pintype "bidirectional"))
      (node (ref "SV1") (pin "2") (pinfunction "2_2") (pintype "passive"))
    )
    (net (code "62") (name "RX_CCTALK") (class "Default")
      (node (ref "D5") (pin "A") (pinfunction "A_A") (pintype "passive"))
      (node (ref "IC4") (pin "4") (pinfunction "A_4") (pintype "tri_state"))
      (node (ref "R25") (pin "1") (pinfunction "1_1") (pintype "passive"))
      (node (ref "SV1") (pin "1") (pinfunction "1_1") (pintype "passive"))
    )
    (net (code "63") (name "RX_MDB") (class "Default")
      (node (ref "IC4") (pin "1") (pinfunction "A_1") (pintype "tri_state"))
      (node (ref "IC5") (pin "3") (pinfunction "O_3") (pintype "output"))
      (node (ref "R4") (pin "1") (pinfunction "1_1") (pintype "passive"))
      (node (ref "SV1") (pin "3") (pinfunction "3_3") (pintype "passive"))
    )
    (net (code "64") (name "TX_CCTALK") (class "Default")
      (node (ref "MICRO") (pin "TX") (pinfunction "D1/TX_TX") (pintype "bidirectional"))
      (node (ref "R27") (pin "2") (pinfunction "2_2") (pintype "passive"))
    )
    (net (code "65") (name "TX_MDB") (class "Default")
      (node (ref "MICRO") (pin "MOSI") (pinfunction "MOSI_MOSI") (pintype "bidirectional"))
      (node (ref "R6") (pin "1") (pinfunction "1_1") (pintype "passive"))
    )
    (net (code "66") (name "unconnected-(CCTALKC-KL-Pad2)") (class "Default")
      (node (ref "CCTALK") (pin "2") (pinfunction "KL_2") (pintype "passive"))
    )
    (net (code "67") (name "unconnected-(CCTALKD-KL-Pad3)") (class "Default")
      (node (ref "CCTALK") (pin "3") (pinfunction "KL_3") (pintype "passive"))
    )
    (net (code "68") (name "unconnected-(CCTALKF-KL-Pad5)") (class "Default")
      (node (ref "CCTALK") (pin "5") (pinfunction "KL_5") (pintype "passive"))
    )
    (net (code "69") (name "unconnected-(CCTALKG-KL-Pad6)") (class "Default")
      (node (ref "CCTALK") (pin "6") (pinfunction "KL_6") (pintype "passive"))
    )
    (net (code "70") (name "unconnected-(CCTALKJ-KL-Pad9)") (class "Default")
      (node (ref "CCTALK") (pin "9") (pinfunction "KL_9") (pintype "passive"))
    )
    (net (code "71") (name "unconnected-(K1-PadO)") (class "Default")
      (node (ref "K1") (pin "O") (pinfunction "O_O") (pintype "passive"))
    )
    (net (code "72") (name "unconnected-(K2-PadO)") (class "Default")
      (node (ref "K2") (pin "O") (pinfunction "O_O") (pintype "passive"))
    )
    (net (code "73") (name "unconnected-(MDBC-S-Pad3)") (class "Default")
      (node (ref "MDB") (pin "3") (pinfunction "S_3") (pintype "passive"))
    )
    (net (code "74") (name "unconnected-(MICRO-3V-Pad3V3)") (class "Default")
      (node (ref "MICRO") (pin "3V3") (pinfunction "3V_3V3") (pintype "bidirectional"))
    )
    (net (code "75") (name "unconnected-(MICRO-AREF-PadREF)") (class "Default")
      (node (ref "MICRO") (pin "REF") (pinfunction "AREF_REF") (pintype "bidirectional"))
    )
    (net (code "76") (name "unconnected-(MICRO-Pad5V)") (class "Default")
      (node (ref "MICRO") (pin "5V") (pinfunction "5V_5V") (pintype "bidirectional"))
    )
    (net (code "77") (name "unconnected-(MICRO-PadA0)") (class "Default")
      (node (ref "MICRO") (pin "A0") (pinfunction "A0_A0") (pintype "bidirectional"))
    )
    (net (code "78") (name "unconnected-(MICRO-PadA2)") (class "Default")
      (node (ref "MICRO") (pin "A2") (pinfunction "A2_A2") (pintype "bidirectional"))
    )
    (net (code "79") (name "unconnected-(MICRO-PadA3)") (class "Default")
      (node (ref "MICRO") (pin "A3") (pinfunction "A3_A3") (pintype "bidirectional"))
    )
    (net (code "80") (name "unconnected-(MICRO-PadA4)") (class "Default")
      (node (ref "MICRO") (pin "A4") (pinfunction "A4_A4") (pintype "bidirectional"))
    )
    (net (code "81") (name "unconnected-(MICRO-PadNC7)") (class "Default")
      (node (ref "MICRO") (pin "NC7") (pinfunction "NC7_NC7") (pintype "bidirectional"))
    )
    (net (code "82") (name "unconnected-(MICRO-PadNC8)") (class "Default")
      (node (ref "MICRO") (pin "NC8") (pinfunction "NC8_NC8") (pintype "bidirectional"))
    )
    (net (code "83") (name "unconnected-(MICRO-PadSCK)") (class "Default")
      (node (ref "MICRO") (pin "SCK") (pinfunction "SCK_SCK") (pintype "bidirectional"))
    )
    (net (code "84") (name "unconnected-(MICRO-RESET-PadRST)") (class "Default")
      (node (ref "MICRO") (pin "RST") (pinfunction "RESET_RST") (pintype "bidirectional"))
    )
    (net (code "85") (name "unconnected-(MICRO-RESET1-PadRST1)") (class "Default")
      (node (ref "MICRO") (pin "RST1") (pinfunction "RESET1_RST1") (pintype "bidirectional"))
    )
    (net (code "86") (name "unconnected-(MICRO-RXLED{slash}SS-PadSS)") (class "Default")
      (node (ref "MICRO") (pin "SS") (pinfunction "RXLED/SS_SS") (pintype "bidirectional"))
    )
    (net (code "87") (name "unconnected-(OP1-BAS-Pad6)") (class "Default")
      (node (ref "OP1") (pin "6") (pinfunction "BAS_6") (pintype "passive"))
    )
    (net (code "88") (name "unconnected-(OP2-BAS-Pad6)") (class "Default")
      (node (ref "OP2") (pin "6") (pinfunction "BAS_6") (pintype "passive"))
    )
    (net (code "89") (name "unconnected-(OP3-BAS-Pad6)") (class "Default")
      (node (ref "OP3") (pin "6") (pinfunction "BAS_6") (pintype "passive"))
    )
  )
)
